# Candle-V01-005.net
KiCad netlist of a schematic drawn in EAGLE
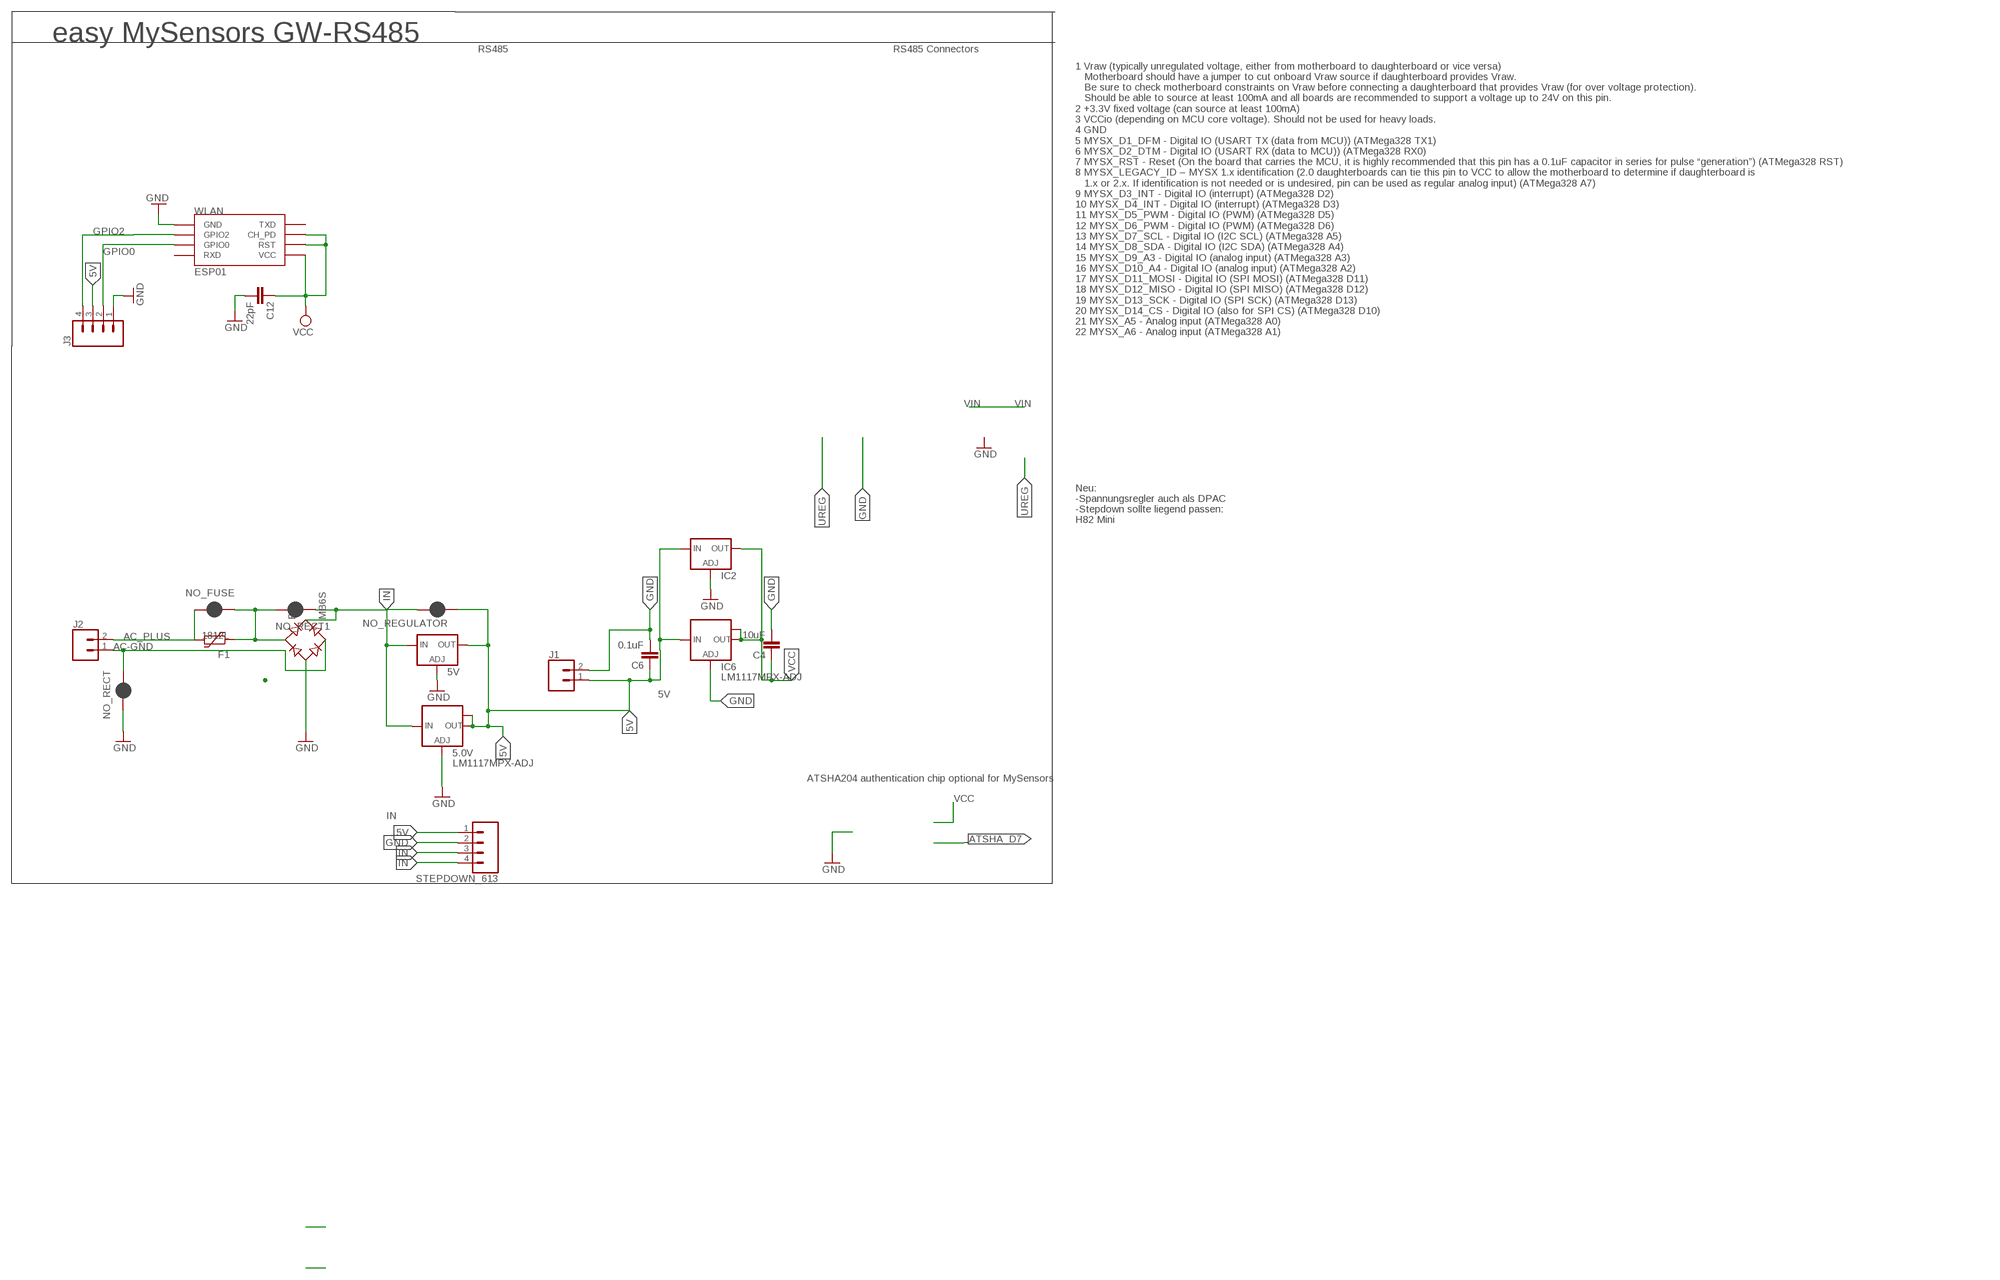
[diagram p0: schematic, sheet 1]

(export (version "E")
  (design (tool "Eeschema 10.0.6"))
  (components
    (comp (ref "5.0V")
      (value "LM1117MPX-ADJ")
      (footprint "eagle-import:SOT223")
      (libsource (lib "eagle-import") (part "LM1117MPX-ADJ"))
    )
    (comp (ref "5V")
      (value "LD117ADT50TR")
      (footprint "eagle-import:DPACK")
      (libsource (lib "eagle-import") (part "LD117A?DT50TR"))
    )
    (comp (ref "B1")
      (value "MB6S")
      (footprint "eagle-import:SOIC-4")
      (libsource (lib "eagle-import") (part "MBS6"))
    )
    (comp (ref "C4")
      (value "10uF")
      (footprint "eagle-import:C1210")
      (libsource (lib "eagle-import") (part "C-EUC1210"))
    )
    (comp (ref "C6")
      (value "0.1uF")
      (footprint "eagle-import:C1206")
      (libsource (lib "eagle-import") (part "C-EUC1206"))
    )
    (comp (ref "C12")
      (value "22pF")
      (footprint "eagle-import:C0805")
      (libsource (lib "eagle-import") (part "C-EUC0805"))
    )
    (comp (ref "F1")
      (value "1812L")
      (footprint "eagle-import:1812L")
      (libsource (lib "eagle-import") (part "1812L"))
    )
    (comp (ref "IC2")
      (value "LD117ADT50TR")
      (footprint "eagle-import:DPACK")
      (libsource (lib "eagle-import") (part "LD117A?DT50TR"))
    )
    (comp (ref "IC6")
      (value "LM1117MPX-ADJ")
      (footprint "eagle-import:SOT223")
      (libsource (lib "eagle-import") (part "LM1117MPX-ADJ"))
    )
    (comp (ref "J1")
      (value "CONN_02PTH3")
      (footprint "eagle-import:1X02_LONGPADS")
      (libsource (lib "eagle-import") (part "CONN_02PTH3"))
    )
    (comp (ref "J2")
      (value "CONN_02PTH3")
      (footprint "eagle-import:1X02_LONGPADS")
      (libsource (lib "eagle-import") (part "CONN_02PTH3"))
    )
    (comp (ref "J3")
      (value "CONN_04LONGPADS")
      (footprint "eagle-import:1X04_LONGPADS")
      (libsource (lib "eagle-import") (part "CONN_04LONGPADS"))
    )
    (comp (ref "NO_FUSE")
      (value "JUMPER-SMT_2_NC_PASTE_NO-SILK")
      (footprint "eagle-import:SMT-JUMPER_2_NC_PASTE_NO-SILK")
      (libsource (lib "eagle-import") (part "JUMPER-SMT_2_NC_PASTE_NO-SILK"))
    )
    (comp (ref "NO_RECT")
      (value "JUMPER-SMT_2_NC_PASTE_NO-SILK")
      (footprint "eagle-import:SMT-JUMPER_2_NC_PASTE_NO-SILK")
      (libsource (lib "eagle-import") (part "JUMPER-SMT_2_NC_PASTE_NO-SILK"))
    )
    (comp (ref "NO_RECT1")
      (value "JUMPER-SMT_2_NC_PASTE_NO-SILK")
      (footprint "eagle-import:SMT-JUMPER_2_NC_PASTE_NO-SILK")
      (libsource (lib "eagle-import") (part "JUMPER-SMT_2_NC_PASTE_NO-SILK"))
    )
    (comp (ref "NO_REGULATOR")
      (value "JUMPER-SMT_2_NC_PASTE_NO-SILK")
      (footprint "eagle-import:SMT-JUMPER_2_NC_PASTE_NO-SILK")
      (libsource (lib "eagle-import") (part "JUMPER-SMT_2_NC_PASTE_NO-SILK"))
    )
    (comp (ref "STEPDOWN_613")
      (value "CONN_04")
      (footprint "eagle-import:1X04")
      (libsource (lib "eagle-import") (part "CONN_04"))
    )
    (comp (ref "WLAN")
      (value "ESP01")
      (footprint "eagle-import:ESP01")
      (libsource (lib "eagle-import") (part "ESP01"))
    )
  )
  (nets
    (net (code "1") (name "/AC-GND") (class "Default")
      (node (ref "B1") (pin "~2") (pinfunction "AC2_~2") (pintype "passive"))
      (node (ref "J2") (pin "1") (pinfunction "1_1") (pintype "passive"))
      (node (ref "NO_RECT") (pin "1") (pinfunction "1_1") (pintype "passive"))
    )
    (net (code "2") (name "/AC_PLUS") (class "Default")
      (node (ref "F1") (pin "P$2") (pinfunction "2_P$2") (pintype "passive"))
      (node (ref "J2") (pin "2") (pinfunction "2_2") (pintype "passive"))
      (node (ref "NO_FUSE") (pin "2") (pinfunction "2_2") (pintype "passive"))
    )
    (net (code "4") (name "/GPIO0") (class "Default")
      (node (ref "J3") (pin "2") (pinfunction "2_2") (pintype "passive"))
      (node (ref "WLAN") (pin "GPIO0") (pinfunction "GPIO0_GPIO0") (pintype "bidirectional"))
    )
    (net (code "5") (name "/GPIO2") (class "Default")
      (node (ref "J3") (pin "4") (pinfunction "4_4") (pintype "passive"))
      (node (ref "WLAN") (pin "GPIO2") (pinfunction "GPIO2_GPIO2") (pintype "bidirectional"))
    )
    (net (code "7") (name "5V") (class "Default")
      (node (ref "5.0V") (pin "2") (pinfunction "OUT_2") (pintype "passive"))
      (node (ref "5.0V") (pin "TAB") (pinfunction "OUT1_TAB") (pintype "passive"))
      (node (ref "5V") (pin "4") (pinfunction "OUT_4") (pintype "passive"))
      (node (ref "C6") (pin "1") (pinfunction "1_1") (pintype "passive"))
      (node (ref "IC2") (pin "3") (pinfunction "IN_3") (pintype "input"))
      (node (ref "IC6") (pin "3") (pinfunction "IN_3") (pintype "input"))
      (node (ref "J1") (pin "1") (pinfunction "1_1") (pintype "passive"))
      (node (ref "J3") (pin "3") (pinfunction "3_3") (pintype "passive"))
      (node (ref "NO_REGULATOR") (pin "1") (pinfunction "1_1") (pintype "passive"))
      (node (ref "STEPDOWN_613") (pin "1") (pinfunction "1_1") (pintype "passive"))
    )
    (net (code "8") (name "GND") (class "Default")
      (node (ref "5.0V") (pin "1") (pinfunction "ADJ_1") (pintype "input"))
      (node (ref "5V") (pin "1") (pinfunction "ADJ_1") (pintype "input"))
      (node (ref "B1") (pin "-") (pinfunction "-_-") (pintype "passive"))
      (node (ref "C12") (pin "2") (pinfunction "2_2") (pintype "passive"))
      (node (ref "C4") (pin "2") (pinfunction "2_2") (pintype "passive"))
      (node (ref "C6") (pin "2") (pinfunction "2_2") (pintype "passive"))
      (node (ref "IC2") (pin "1") (pinfunction "ADJ_1") (pintype "input"))
      (node (ref "IC6") (pin "1") (pinfunction "ADJ_1") (pintype "input"))
      (node (ref "J1") (pin "2") (pinfunction "2_2") (pintype "passive"))
      (node (ref "J3") (pin "1") (pinfunction "1_1") (pintype "passive"))
      (node (ref "NO_RECT") (pin "2") (pinfunction "2_2") (pintype "passive"))
      (node (ref "STEPDOWN_613") (pin "2") (pinfunction "2_2") (pintype "passive"))
      (node (ref "WLAN") (pin "GND") (pinfunction "GND_GND") (pintype "bidirectional"))
    )
    (net (code "9") (name "IN") (class "Default")
      (node (ref "5.0V") (pin "3") (pinfunction "IN_3") (pintype "input"))
      (node (ref "5V") (pin "3") (pinfunction "IN_3") (pintype "input"))
      (node (ref "B1") (pin "+") (pinfunction "+_+") (pintype "passive"))
      (node (ref "NO_RECT1") (pin "2") (pinfunction "2_2") (pintype "passive"))
      (node (ref "NO_REGULATOR") (pin "2") (pinfunction "2_2") (pintype "passive"))
      (node (ref "STEPDOWN_613") (pin "3") (pinfunction "3_3") (pintype "passive"))
      (node (ref "STEPDOWN_613") (pin "4") (pinfunction "4_4") (pintype "passive"))
    )
    (net (code "10") (name "Net-(B1-AC1)") (class "Default")
      (node (ref "B1") (pin "~1") (pinfunction "AC1_~1") (pintype "passive"))
      (node (ref "F1") (pin "P$1") (pinfunction "1_P$1") (pintype "passive"))
      (node (ref "NO_FUSE") (pin "1") (pinfunction "1_1") (pintype "passive"))
      (node (ref "NO_RECT1") (pin "1") (pinfunction "1_1") (pintype "passive"))
    )
    (net (code "12") (name "VCC") (class "Default")
      (node (ref "C12") (pin "1") (pinfunction "1_1") (pintype "passive"))
      (node (ref "C4") (pin "1") (pinfunction "1_1") (pintype "passive"))
      (node (ref "IC2") (pin "4") (pinfunction "OUT_4") (pintype "passive"))
      (node (ref "IC6") (pin "2") (pinfunction "OUT_2") (pintype "passive"))
      (node (ref "IC6") (pin "TAB") (pinfunction "OUT1_TAB") (pintype "passive"))
      (node (ref "WLAN") (pin "CH_PD") (pinfunction "CH_PD_CH_PD") (pintype "bidirectional"))
      (node (ref "WLAN") (pin "RST") (pinfunction "RST_RST") (pintype "bidirectional"))
      (node (ref "WLAN") (pin "VCC") (pinfunction "VCC_VCC") (pintype "bidirectional"))
    )
    (net (code "13") (name "unconnected-(WLAN-RXD-PadRX)") (class "Default")
      (node (ref "WLAN") (pin "RX") (pinfunction "RXD_RX") (pintype "bidirectional"))
    )
    (net (code "14") (name "unconnected-(WLAN-TXD-PadTX)") (class "Default")
      (node (ref "WLAN") (pin "TX") (pinfunction "TXD_TX") (pintype "bidirectional"))
    )
  )
)
